# stm32b.net
KiCad netlist of a schematic drawn in Altium Designer
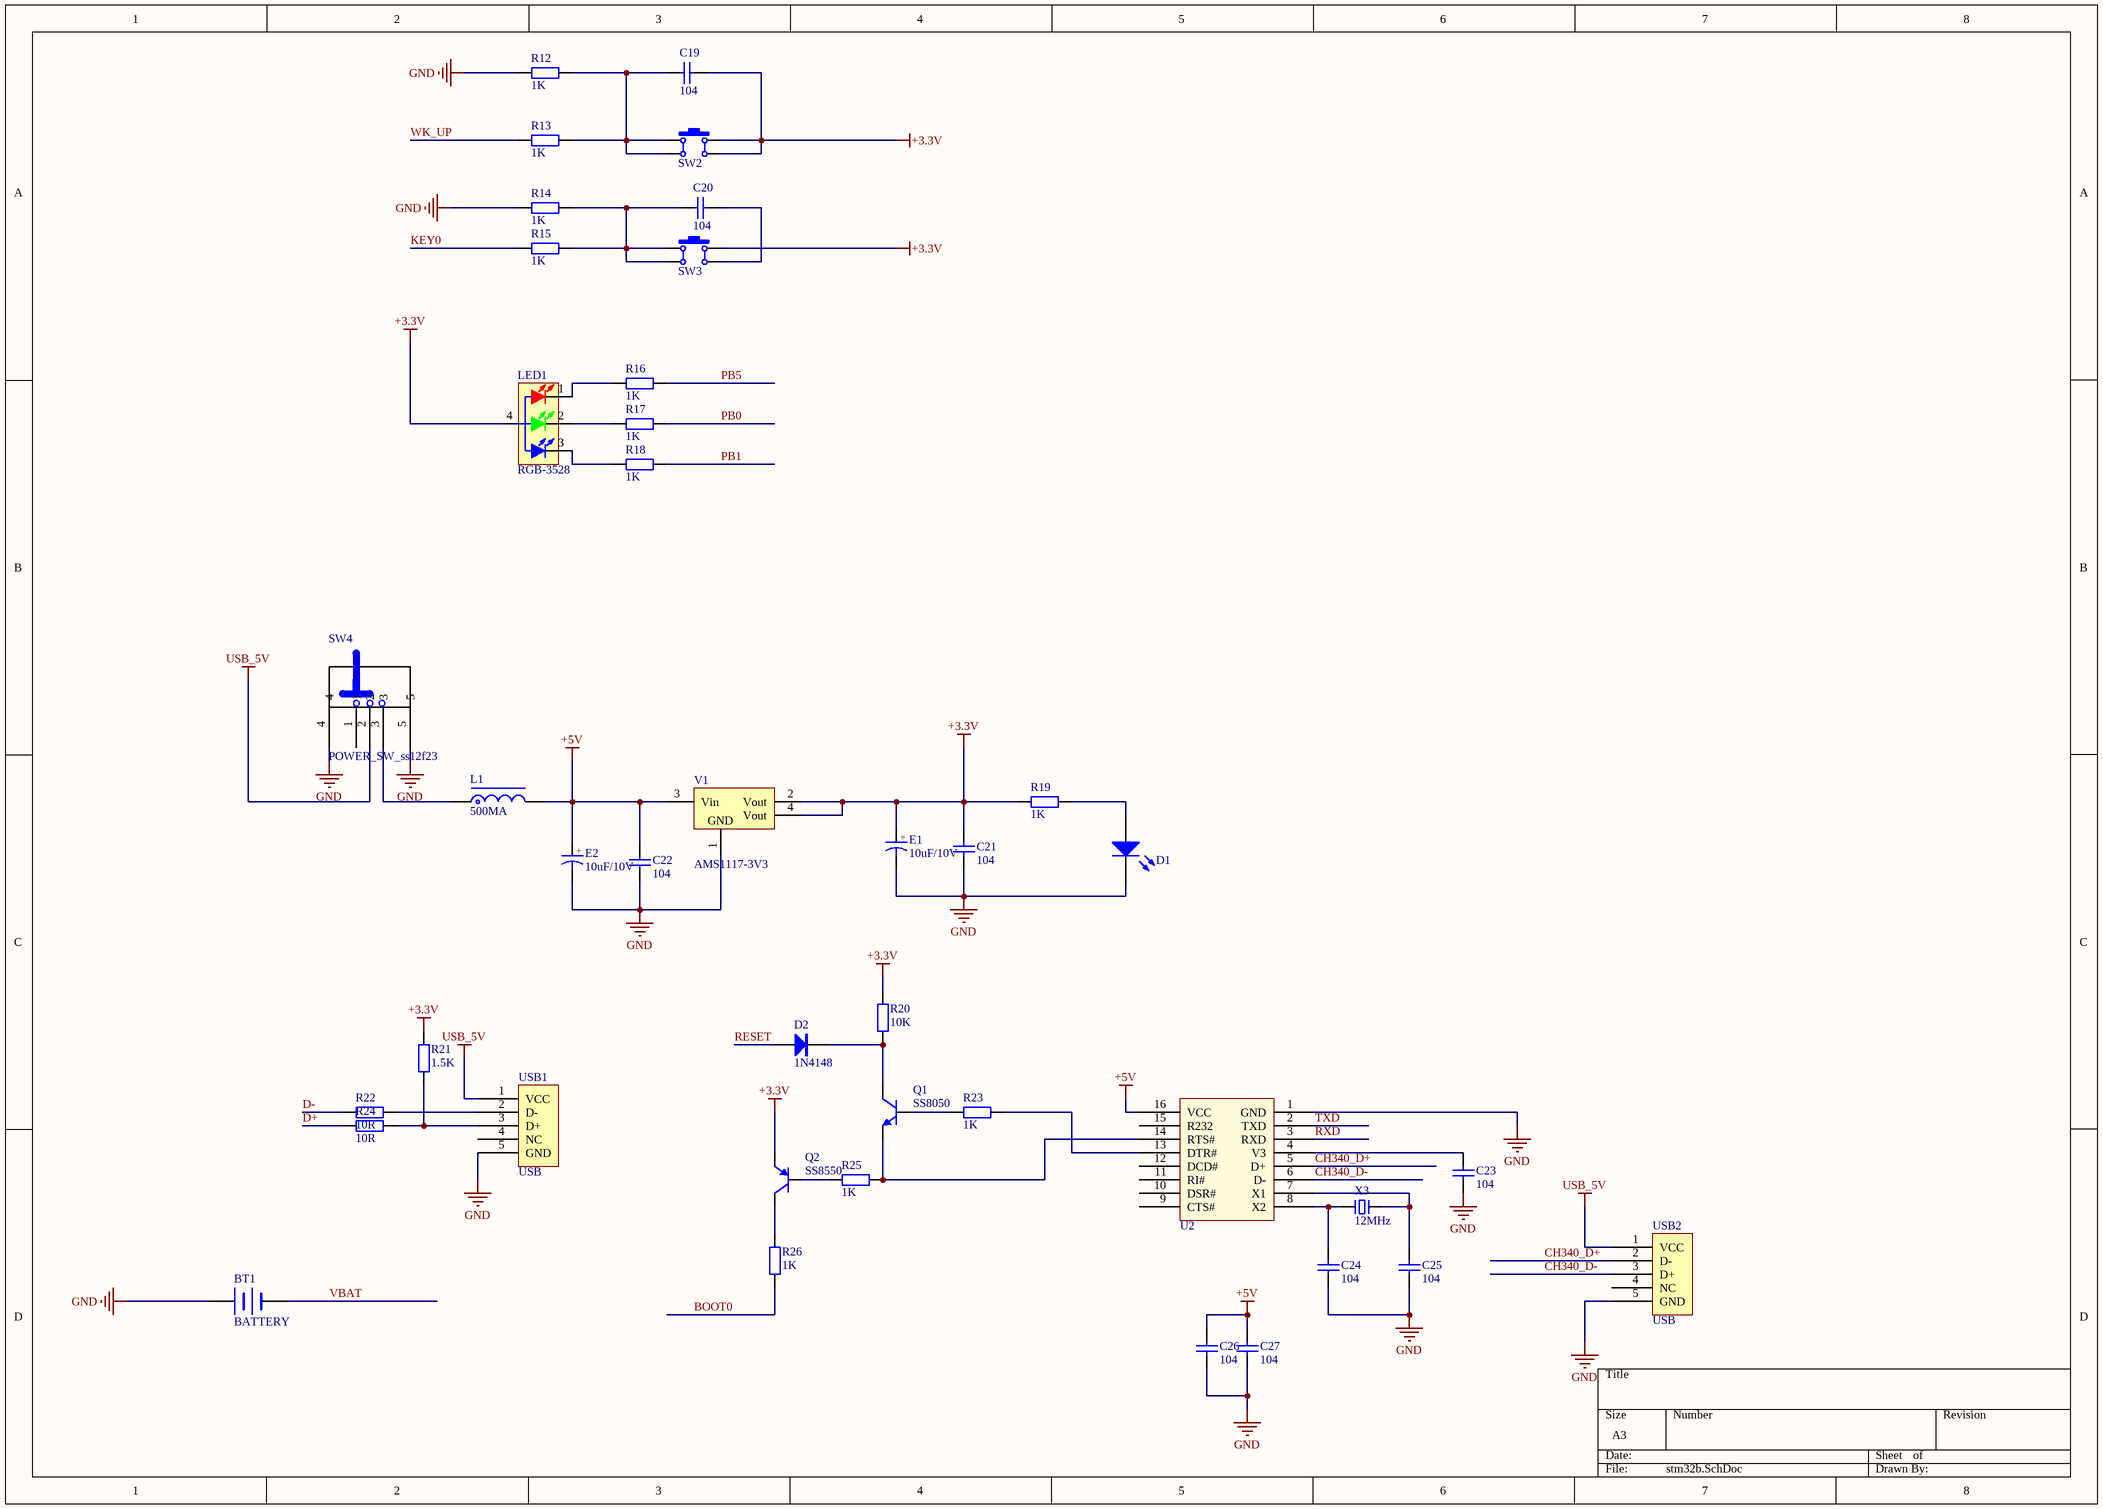
[diagram p0: stm32b.SchDoc]

(export (version "E")
  (design (tool "Eeschema 10.0.6"))
  (components
    (comp (ref "BT1")
      (value "BATTERY")
      (footprint "CR1220-2 电池卧式底座")
      (description "Battery")
      (libsource (lib "stm32") (part "BATTERY"))
    )
    (comp (ref "C19")
      (value "104")
      (footprint "1210")
      (description "贴片电容")
      (libsource (lib "stm32") (part "C"))
    )
    (comp (ref "C20")
      (value "104")
      (footprint "1210")
      (description "贴片电容")
      (libsource (lib "stm32") (part "C"))
    )
    (comp (ref "C21")
      (value "104")
      (footprint "1210")
      (description "贴片电容")
      (libsource (lib "stm32") (part "C"))
    )
    (comp (ref "C22")
      (value "104")
      (footprint "1210")
      (description "贴片电容")
      (libsource (lib "stm32") (part "C"))
    )
    (comp (ref "C23")
      (value "104")
      (footprint "1210")
      (description "贴片电容")
      (libsource (lib "stm32") (part "C"))
    )
    (comp (ref "C24")
      (value "104")
      (footprint "1210")
      (description "贴片电容")
      (libsource (lib "stm32") (part "C"))
    )
    (comp (ref "C25")
      (value "104")
      (footprint "1210")
      (description "贴片电容")
      (libsource (lib "stm32") (part "C"))
    )
    (comp (ref "C26")
      (value "104")
      (footprint "1210")
      (description "贴片电容")
      (libsource (lib "stm32") (part "C"))
    )
    (comp (ref "C27")
      (value "104")
      (footprint "1210")
      (description "贴片电容")
      (libsource (lib "stm32") (part "C"))
    )
    (comp (ref "D1")
      (value "LED")
      (footprint "0805")
      (description "发光二极管")
      (libsource (lib "Miscellaneous Devices") (part "LED"))
    )
    (comp (ref "D2")
      (value "1N4148")
      (footprint "DO-204AH(DO-35)")
      (description "开关二极管")
      (libsource (lib "stm32") (part "1N4148"))
    )
    (comp (ref "E1")
      (value "10uF/10V")
      (footprint "C65225")
      (description "贴片电解电容")
      (libsource (lib "stm32") (part "CE_SMD"))
    )
    (comp (ref "E2")
      (value "10uF/10V")
      (footprint "C65225")
      (description "贴片电解电容")
      (libsource (lib "stm32") (part "CE_SMD"))
    )
    (comp (ref "L1")
      (value "500MA")
      (footprint "0805")
      (description "一体成型电感")
      (libsource (lib "stm32") (part "L-Molding Choke"))
    )
    (comp (ref "LED1")
      (value "RGB-3528")
      (footprint "led3色")
      (description "3528三基色LED")
      (libsource (lib "stm32") (part "LED-RGB 3528"))
    )
    (comp (ref "Q1")
      (value "SS8050")
      (footprint "SOT-23")
      (description "高频放大-NPN型")
      (libsource (lib "stm32") (part "8050-SMD"))
    )
    (comp (ref "Q2")
      (value "SS8550")
      (footprint "SOT-23")
      (description "高频放大-PNP型")
      (libsource (lib "stm32") (part "8550-SMD"))
    )
    (comp (ref "R12")
      (value "1K")
      (footprint "R1206-HP_L")
      (description "贴片电阻")
      (libsource (lib "stm32") (part "R"))
    )
    (comp (ref "R13")
      (value "1K")
      (footprint "R1206-HP_L")
      (description "贴片电阻")
      (libsource (lib "stm32") (part "R"))
    )
    (comp (ref "R14")
      (value "1K")
      (footprint "R1206-HP_L")
      (description "贴片电阻")
      (libsource (lib "stm32") (part "R"))
    )
    (comp (ref "R15")
      (value "1K")
      (footprint "R1206-HP_L")
      (description "贴片电阻")
      (libsource (lib "stm32") (part "R"))
    )
    (comp (ref "R16")
      (value "1K")
      (footprint "R1206-HP_L")
      (description "贴片电阻")
      (libsource (lib "stm32") (part "R"))
    )
    (comp (ref "R17")
      (value "1K")
      (footprint "R1206-HP_L")
      (description "贴片电阻")
      (libsource (lib "stm32") (part "R"))
    )
    (comp (ref "R18")
      (value "1K")
      (footprint "R1206-HP_L")
      (description "贴片电阻")
      (libsource (lib "stm32") (part "R"))
    )
    (comp (ref "R19")
      (value "1K")
      (footprint "R1206-HP_L")
      (description "贴片电阻")
      (libsource (lib "stm32") (part "R"))
    )
    (comp (ref "R20")
      (value "10K")
      (footprint "R1206-HP_L")
      (description "贴片电阻")
      (libsource (lib "stm32") (part "R"))
    )
    (comp (ref "R21")
      (value "1.5K")
      (footprint "R1206-HP_L")
      (description "贴片电阻")
      (libsource (lib "stm32") (part "R"))
    )
    (comp (ref "R22")
      (value "10R")
      (footprint "R1206-HP_L")
      (description "贴片电阻")
      (libsource (lib "stm32") (part "R"))
    )
    (comp (ref "R23")
      (value "1K")
      (footprint "R1206-HP_L")
      (description "贴片电阻")
      (libsource (lib "stm32") (part "R"))
    )
    (comp (ref "R24")
      (value "10R")
      (footprint "R1206-HP_L")
      (description "贴片电阻")
      (libsource (lib "stm32") (part "R"))
    )
    (comp (ref "R25")
      (value "1K")
      (footprint "R1206-HP_L")
      (description "贴片电阻")
      (libsource (lib "stm32") (part "R"))
    )
    (comp (ref "R26")
      (value "1K")
      (footprint "R1206-HP_L")
      (description "贴片电阻")
      (libsource (lib "stm32") (part "R"))
    )
    (comp (ref "SW2")
      (value "4x4x1.5")
      (footprint "按键")
      (description "贴片4x4轻触开关")
      (libsource (lib "stm32") (part "TSW SMD-4x4"))
    )
    (comp (ref "SW3")
      (value "4x4x1.5")
      (footprint "按键")
      (description "贴片4x4轻触开关")
      (libsource (lib "stm32") (part "TSW SMD-4x4"))
    )
    (comp (ref "SW4")
      (value "POWER_SW_ss12f23")
      (footprint "SS-12F23")
      (libsource (lib "stm32") (part "POWER_SW_ss12f23"))
    )
    (comp (ref "U2") (value "CH340G") (footprint "SOP16") (libsource (lib "stm32") (part "CH340G")))
    (comp (ref "USB1") (value "USB") (footprint "MICRO USB 5S B 型") (libsource (lib "stm32") (part "USB")))
    (comp (ref "USB2") (value "USB") (footprint "MICRO USB 5S B 型") (libsource (lib "stm32") (part "USB")))
    (comp (ref "V1")
      (value "AMS1117-3V3")
      (footprint "AMS1117-3.3")
      (description "三端稳压芯片")
      (libsource (lib "stm32") (part "AMS1117"))
    )
    (comp (ref "X3")
      (value "12MHz")
      (footprint "HC-49S")
      (description "2脚无源脚晶振")
      (libsource (lib "stm32") (part "XTAL-2P"))
    )
  )
  (nets
    (net (code "1") (name "+3.3V") (class "Default")
      (node (ref "C19") (pin "2") (pinfunction "2_2") (pintype "passive"))
      (node (ref "C21") (pin "2") (pinfunction "2_2") (pintype "passive"))
      (node (ref "E1") (pin "1") (pinfunction "1_1") (pintype "passive"))
      (node (ref "LED1") (pin "4") (pinfunction "A_4") (pintype "passive"))
      (node (ref "Q2") (pin "2") (pinfunction "E_2") (pintype "passive"))
      (node (ref "R19") (pin "2") (pinfunction "2_2") (pintype "passive"))
      (node (ref "R20") (pin "1") (pinfunction "1_1") (pintype "passive"))
      (node (ref "R21") (pin "2") (pinfunction "2_2") (pintype "passive"))
      (node (ref "SW2") (pin "2") (pinfunction "2_2") (pintype "passive"))
      (node (ref "SW2") (pin "3") (pinfunction "3_3") (pintype "passive"))
      (node (ref "SW3") (pin "2") (pinfunction "2_2") (pintype "passive"))
      (node (ref "V1") (pin "2") (pinfunction "Vout_2") (pintype "passive"))
      (node (ref "V1") (pin "4") (pinfunction "Vout_4") (pintype "passive"))
    )
    (net (code "2") (name "+5V") (class "Default")
      (node (ref "C22") (pin "2") (pinfunction "2_2") (pintype "passive"))
      (node (ref "C26") (pin "2") (pinfunction "2_2") (pintype "passive"))
      (node (ref "C27") (pin "2") (pinfunction "2_2") (pintype "passive"))
      (node (ref "E2") (pin "1") (pinfunction "1_1") (pintype "passive"))
      (node (ref "L1") (pin "2") (pinfunction "2_2") (pintype "passive"))
      (node (ref "U2") (pin "16") (pinfunction "VCC_16") (pintype "passive"))
      (node (ref "V1") (pin "3") (pinfunction "Vin_3") (pintype "passive"))
    )
    (net (code "3") (name "/BOOT0") (class "Default")
      (node (ref "R26") (pin "1") (pinfunction "1_1") (pintype "passive"))
    )
    (net (code "4") (name "/CH340_D+") (class "Default")
      (node (ref "U2") (pin "5") (pinfunction "D+_5") (pintype "passive"))
      (node (ref "USB2") (pin "2") (pinfunction "D-_2") (pintype "passive"))
    )
    (net (code "5") (name "/CH340_D-") (class "Default")
      (node (ref "U2") (pin "6") (pinfunction "D-_6") (pintype "passive"))
      (node (ref "USB2") (pin "3") (pinfunction "D+_3") (pintype "passive"))
    )
    (net (code "6") (name "/D+") (class "Default")
      (node (ref "R24") (pin "2") (pinfunction "2_2") (pintype "passive"))
    )
    (net (code "7") (name "/D-") (class "Default")
      (node (ref "R22") (pin "2") (pinfunction "2_2") (pintype "passive"))
    )
    (net (code "8") (name "/KEY0") (class "Default")
      (node (ref "R15") (pin "2") (pinfunction "2_2") (pintype "passive"))
    )
    (net (code "9") (name "/PB0") (class "Default")
      (node (ref "R17") (pin "1") (pinfunction "1_1") (pintype "passive"))
    )
    (net (code "10") (name "/PB1") (class "Default")
      (node (ref "R18") (pin "1") (pinfunction "1_1") (pintype "passive"))
    )
    (net (code "11") (name "/PB5") (class "Default")
      (node (ref "R16") (pin "1") (pinfunction "1_1") (pintype "passive"))
    )
    (net (code "12") (name "/RESET") (class "Default")
      (node (ref "D2") (pin "1") (pinfunction "A_1") (pintype "passive"))
    )
    (net (code "13") (name "/RXD") (class "Default")
      (node (ref "U2") (pin "3") (pinfunction "RXD_3") (pintype "passive"))
    )
    (net (code "14") (name "/TXD") (class "Default")
      (node (ref "U2") (pin "2") (pinfunction "TXD_2") (pintype "passive"))
    )
    (net (code "15") (name "/VBAT") (class "Default")
      (node (ref "BT1") (pin "2") (pinfunction "-_2") (pintype "passive"))
    )
    (net (code "16") (name "/WK_UP") (class "Default")
      (node (ref "R13") (pin "2") (pinfunction "2_2") (pintype "passive"))
    )
    (net (code "17") (name "GND") (class "Default")
      (node (ref "BT1") (pin "1") (pinfunction "+_1") (pintype "passive"))
      (node (ref "C21") (pin "1") (pinfunction "1_1") (pintype "passive"))
      (node (ref "C22") (pin "1") (pinfunction "1_1") (pintype "passive"))
      (node (ref "C23") (pin "1") (pinfunction "1_1") (pintype "passive"))
      (node (ref "C24") (pin "2") (pinfunction "2_2") (pintype "passive"))
      (node (ref "C25") (pin "1") (pinfunction "1_1") (pintype "passive"))
      (node (ref "C26") (pin "1") (pinfunction "1_1") (pintype "passive"))
      (node (ref "C27") (pin "1") (pinfunction "1_1") (pintype "passive"))
      (node (ref "D1") (pin "2") (pinfunction "K_2") (pintype "passive"))
      (node (ref "E1") (pin "2") (pinfunction "2_2") (pintype "passive"))
      (node (ref "E2") (pin "2") (pinfunction "2_2") (pintype "passive"))
      (node (ref "R12") (pin "2") (pinfunction "2_2") (pintype "passive"))
      (node (ref "R14") (pin "2") (pinfunction "2_2") (pintype "passive"))
      (node (ref "SW4") (pin "4") (pinfunction "4_4") (pintype "passive"))
      (node (ref "SW4") (pin "5") (pinfunction "5_5") (pintype "passive"))
      (node (ref "U2") (pin "1") (pinfunction "GND_1") (pintype "passive"))
      (node (ref "USB1") (pin "5") (pinfunction "GND_5") (pintype "passive"))
      (node (ref "USB2") (pin "5") (pinfunction "GND_5") (pintype "passive"))
      (node (ref "V1") (pin "1") (pinfunction "GND_1") (pintype "passive"))
    )
    (net (code "18") (name "Net-(C19-Pad1)") (class "Default")
      (node (ref "C19") (pin "1") (pinfunction "1_1") (pintype "passive"))
      (node (ref "R12") (pin "1") (pinfunction "1_1") (pintype "passive"))
      (node (ref "R13") (pin "1") (pinfunction "1_1") (pintype "passive"))
      (node (ref "SW2") (pin "1") (pinfunction "1_1") (pintype "passive"))
      (node (ref "SW2") (pin "4") (pinfunction "4_4") (pintype "passive"))
    )
    (net (code "19") (name "Net-(C20-Pad1)") (class "Default")
      (node (ref "C20") (pin "1") (pinfunction "1_1") (pintype "passive"))
      (node (ref "R14") (pin "1") (pinfunction "1_1") (pintype "passive"))
      (node (ref "R15") (pin "1") (pinfunction "1_1") (pintype "passive"))
      (node (ref "SW3") (pin "1") (pinfunction "1_1") (pintype "passive"))
      (node (ref "SW3") (pin "4") (pinfunction "4_4") (pintype "passive"))
    )
    (net (code "20") (name "Net-(C20-Pad2)") (class "Default")
      (node (ref "C20") (pin "2") (pinfunction "2_2") (pintype "passive"))
      (node (ref "SW3") (pin "3") (pinfunction "3_3") (pintype "passive"))
    )
    (net (code "21") (name "Net-(D1-A)") (class "Default")
      (node (ref "D1") (pin "1") (pinfunction "A_1") (pintype "passive"))
      (node (ref "R19") (pin "1") (pinfunction "1_1") (pintype "passive"))
    )
    (net (code "22") (name "Net-(D2-K)") (class "Default")
      (node (ref "D2") (pin "2") (pinfunction "K_2") (pintype "passive"))
      (node (ref "Q1") (pin "3") (pinfunction "C_3") (pintype "passive"))
      (node (ref "R20") (pin "2") (pinfunction "2_2") (pintype "passive"))
    )
    (net (code "23") (name "Net-(L1-Pad1)") (class "Default")
      (node (ref "L1") (pin "1") (pinfunction "1_1") (pintype "passive"))
      (node (ref "SW4") (pin "3") (pinfunction "3_3") (pintype "passive"))
    )
    (net (code "24") (name "Net-(LED1-BULE_K)") (class "Default")
      (node (ref "LED1") (pin "3") (pinfunction "BULE_K_3") (pintype "passive"))
      (node (ref "R18") (pin "2") (pinfunction "2_2") (pintype "passive"))
    )
    (net (code "25") (name "Net-(LED1-GREEN_K)") (class "Default")
      (node (ref "LED1") (pin "2") (pinfunction "GREEN_K_2") (pintype "passive"))
      (node (ref "R17") (pin "2") (pinfunction "2_2") (pintype "passive"))
    )
    (net (code "26") (name "Net-(LED1-RED_K)") (class "Default")
      (node (ref "LED1") (pin "1") (pinfunction "RED_K_1") (pintype "passive"))
      (node (ref "R16") (pin "2") (pinfunction "2_2") (pintype "passive"))
    )
    (net (code "27") (name "Net-(Q1-B)") (class "Default")
      (node (ref "Q1") (pin "1") (pinfunction "B_1") (pintype "passive"))
      (node (ref "R23") (pin "1") (pinfunction "1_1") (pintype "passive"))
    )
    (net (code "28") (name "Net-(Q1-E)") (class "Default")
      (node (ref "Q1") (pin "2") (pinfunction "E_2") (pintype "passive"))
      (node (ref "R25") (pin "2") (pinfunction "2_2") (pintype "passive"))
      (node (ref "U2") (pin "14") (pinfunction "RTS#_14") (pintype "passive"))
    )
    (net (code "29") (name "Net-(Q2-B)") (class "Default")
      (node (ref "Q2") (pin "1") (pinfunction "B_1") (pintype "passive"))
      (node (ref "R25") (pin "1") (pinfunction "1_1") (pintype "passive"))
    )
    (net (code "30") (name "Net-(Q2-C)") (class "Default")
      (node (ref "Q2") (pin "3") (pinfunction "C_3") (pintype "passive"))
      (node (ref "R26") (pin "2") (pinfunction "2_2") (pintype "passive"))
    )
    (net (code "31") (name "Net-(U2-DTR#)") (class "Default")
      (node (ref "R23") (pin "2") (pinfunction "2_2") (pintype "passive"))
      (node (ref "U2") (pin "13") (pinfunction "DTR#_13") (pintype "passive"))
    )
    (net (code "32") (name "Net-(U2-V3)") (class "Default")
      (node (ref "C23") (pin "2") (pinfunction "2_2") (pintype "passive"))
      (node (ref "U2") (pin "4") (pinfunction "V3_4") (pintype "passive"))
    )
    (net (code "33") (name "Net-(U2-X1)") (class "Default")
      (node (ref "C25") (pin "2") (pinfunction "2_2") (pintype "passive"))
      (node (ref "U2") (pin "7") (pinfunction "X1_7") (pintype "passive"))
      (node (ref "X3") (pin "1") (pinfunction "1_1") (pintype "passive"))
    )
    (net (code "34") (name "Net-(U2-X2)") (class "Default")
      (node (ref "C24") (pin "1") (pinfunction "1_1") (pintype "passive"))
      (node (ref "U2") (pin "8") (pinfunction "X2_8") (pintype "passive"))
      (node (ref "X3") (pin "2") (pinfunction "2_2") (pintype "passive"))
    )
    (net (code "35") (name "Net-(USB1-D+)") (class "Default")
      (node (ref "R21") (pin "1") (pinfunction "1_1") (pintype "passive"))
      (node (ref "R24") (pin "1") (pinfunction "1_1") (pintype "passive"))
      (node (ref "USB1") (pin "3") (pinfunction "D+_3") (pintype "passive"))
    )
    (net (code "36") (name "Net-(USB1-D-)") (class "Default")
      (node (ref "R22") (pin "1") (pinfunction "1_1") (pintype "passive"))
      (node (ref "USB1") (pin "2") (pinfunction "D-_2") (pintype "passive"))
    )
    (net (code "37") (name "USB_5V") (class "Default")
      (node (ref "SW4") (pin "2") (pinfunction "2_2") (pintype "passive"))
      (node (ref "USB1") (pin "1") (pinfunction "VCC_1") (pintype "passive"))
      (node (ref "USB2") (pin "1") (pinfunction "VCC_1") (pintype "passive"))
    )
    (net (code "38") (name "unconnected-(SW4-Pad1)") (class "Default")
      (node (ref "SW4") (pin "1") (pinfunction "1_1") (pintype "passive"))
    )
    (net (code "39") (name "unconnected-(U2-CTS#-Pad9)") (class "Default")
      (node (ref "U2") (pin "9") (pinfunction "CTS#_9") (pintype "passive"))
    )
    (net (code "40") (name "unconnected-(U2-DCD#-Pad12)") (class "Default")
      (node (ref "U2") (pin "12") (pinfunction "DCD#_12") (pintype "passive"))
    )
    (net (code "41") (name "unconnected-(U2-DSR#-Pad10)") (class "Default")
      (node (ref "U2") (pin "10") (pinfunction "DSR#_10") (pintype "passive"))
    )
    (net (code "42") (name "unconnected-(U2-R232-Pad15)") (class "Default")
      (node (ref "U2") (pin "15") (pinfunction "R232_15") (pintype "passive"))
    )
    (net (code "43") (name "unconnected-(U2-RI#-Pad11)") (class "Default")
      (node (ref "U2") (pin "11") (pinfunction "RI#_11") (pintype "passive"))
    )
    (net (code "44") (name "unconnected-(USB1-NC-Pad4)") (class "Default")
      (node (ref "USB1") (pin "4") (pinfunction "NC_4") (pintype "passive"))
    )
    (net (code "45") (name "unconnected-(USB2-NC-Pad4)") (class "Default")
      (node (ref "USB2") (pin "4") (pinfunction "NC_4") (pintype "passive"))
    )
  )
)
